# MCU.net
KiCad netlist of a schematic drawn in Altium Designer
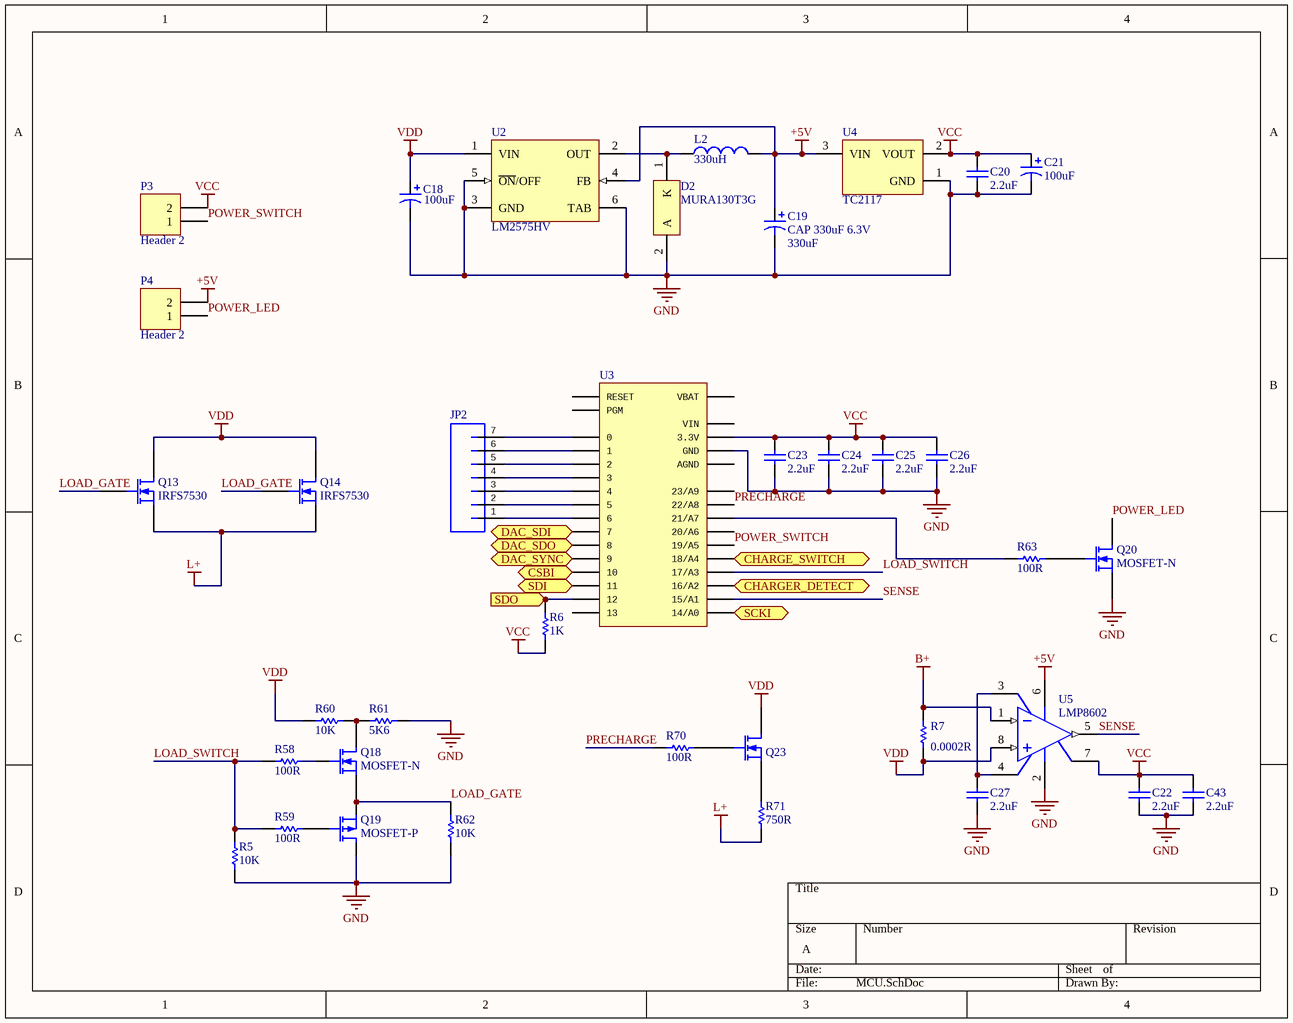
[diagram p0: MCU.SchDoc]

(export (version "E")
  (design (tool "Eeschema 10.0.6"))
  (components
    (comp (ref "C18")
      (value "100uF")
      (footprint "CAP 180uF 50V")
      (description "Polarized Capacitor (Axial)")
      (fields (field (name "PUBLISHER") "Altium Limited"))
      (libsource (lib "Components") (part "CAP 100uF 63V"))
    )
    (comp (ref "C19")
      (value "CAP 330uF 6.3V")
      (footprint "CAP 300uF 6.3V")
      (description "Polarized Capacitor (Axial)")
      (fields (field (name "ALTIUM_VALUE") "330uF") (field (name "PUBLISHER") "Altium Limited"))
      (libsource (lib "Components") (part "CAP 330uF 6.3V"))
    )
    (comp (ref "C20")
      (value "2.2uF")
      (footprint "CAPC0603(1608)55_N")
      (description "CAP 2.2uF 16V Â±10% 0603 (1608 Metric) Thickness 0.55mm SMD")
      (fields (field (name "TOLERANCE") "Â±10%"))
      (libsource (lib "Altium Content Vault") (part "CMP-1035-02762-1"))
    )
    (comp (ref "C21")
      (value "100uF")
      (footprint "AVX-CAPC7343_V")
      (description "Capacitor, Tantalum, 220uF 10% 10V MCCT-D (7343-31)")
      (fields (field (name "PARTNUMBER") "TAJD227K010R") (field (name "MANUFACTURER") "AVX"))
      (libsource (lib "Altium Content Vault") (part "CMP-0279-00002-1"))
    )
    (comp (ref "C22")
      (value "2.2uF")
      (footprint "CAPC0603(1608)55_M")
      (description "CAP 2.2uF 4V Â±10% 0603 (1608 Metric) Thickness 0.55mm SMD")
      (fields (field (name "TOLERANCE") "Â±10%"))
      (libsource (lib "Altium Content Vault") (part "CAP"))
    )
    (comp (ref "C23")
      (value "2.2uF")
      (footprint "CAPC0603(1608)55_N")
      (description "CAP 2.2uF 16V Â±10% 0603 (1608 Metric) Thickness 0.55mm SMD")
      (fields (field (name "TOLERANCE") "Â±10%"))
      (libsource (lib "Altium Content Vault") (part "CMP-1035-02762-1"))
    )
    (comp (ref "C24")
      (value "2.2uF")
      (footprint "CAPC0603(1608)55_N")
      (description "CAP 2.2uF 16V Â±10% 0603 (1608 Metric) Thickness 0.55mm SMD")
      (fields (field (name "TOLERANCE") "Â±10%"))
      (libsource (lib "Altium Content Vault") (part "CMP-1035-02762-1"))
    )
    (comp (ref "C25")
      (value "2.2uF")
      (footprint "CAPC0603(1608)55_N")
      (description "CAP 2.2uF 16V Â±10% 0603 (1608 Metric) Thickness 0.55mm SMD")
      (fields (field (name "TOLERANCE") "Â±10%"))
      (libsource (lib "Altium Content Vault") (part "CMP-1035-02762-1"))
    )
    (comp (ref "C26")
      (value "2.2uF")
      (footprint "CAPC0603(1608)55_N")
      (description "CAP 2.2uF 16V Â±10% 0603 (1608 Metric) Thickness 0.55mm SMD")
      (fields (field (name "TOLERANCE") "Â±10%"))
      (libsource (lib "Altium Content Vault") (part "CMP-1035-02762-1"))
    )
    (comp (ref "C27")
      (value "2.2uF")
      (footprint "CAPC0603(1608)55_N")
      (description "CAP 2.2uF 16V Â±10% 0603 (1608 Metric) Thickness 0.55mm SMD")
      (fields (field (name "TOLERANCE") "Â±10%"))
      (libsource (lib "Altium Content Vault") (part "CMP-1035-02762-1"))
    )
    (comp (ref "C43")
      (value "2.2uF")
      (footprint "CAPC0603(1608)55_M")
      (description "CAP 2.2uF 4V Â±10% 0603 (1608 Metric) Thickness 0.55mm SMD")
      (fields (field (name "TOLERANCE") "Â±10%"))
      (libsource (lib "Altium Content Vault") (part "CAP"))
    )
    (comp (ref "D2")
      (value "MURA130T3G")
      (footprint "ONSC-SMA-2-403D-02_V")
      (description "Surface Mount Ultrafast Power Rectifier, 2-Pin SMA, Pb-Free, Tape and Reel")
      (fields (field (name "MANUFACTURER") "On Semiconductor"))
      (libsource (lib "Altium Content Vault") (part "ONSC-D-K1A2-2_A"))
    )
    (comp (ref "JP2") (value "~") (footprint "JST-7-PTH") (libsource (lib "Components") (part "JST_7_RIGHT")))
    (comp (ref "L2")
      (value "330uH")
      (footprint "SDR1307")
      (description "Inductor")
      (fields (field (name "PUBLISHER") "Altium Limited"))
      (libsource (lib "Components") (part "SDR1307-331KL"))
    )
    (comp (ref "P3")
      (value "Header 2")
      (footprint "HDR1X2")
      (description "Header, 2-Pin")
      (fields (field (name "PUBLISHER") "Altium Limited"))
      (libsource (lib "Miscellaneous Connectors") (part "Header 2"))
    )
    (comp (ref "P4")
      (value "Header 2")
      (footprint "HDR1X2")
      (description "Header, 2-Pin")
      (fields (field (name "PUBLISHER") "Altium Limited"))
      (libsource (lib "Miscellaneous Connectors") (part "Header 2"))
    )
    (comp (ref "Q13")
      (value "IRFS7530")
      (footprint "DPAK127P1525X483-7N")
      (description "N-Channel MOSFET")
      (fields (field (name "PUBLISHER") "Altium Limited"))
      (libsource (lib "Components") (part "IRFS7530"))
    )
    (comp (ref "Q14")
      (value "IRFS7530")
      (footprint "DPAK127P1525X483-7N")
      (description "N-Channel MOSFET")
      (fields (field (name "PUBLISHER") "Altium Limited"))
      (libsource (lib "Components") (part "IRFS7530"))
    )
    (comp (ref "Q18")
      (value "MOSFET-N")
      (footprint "SOT23-3")
      (description "N-Channel MOSFET")
      (fields (field (name "PUBLISHER") "Altium Limited"))
      (libsource (lib "Components") (part "MOSFET-N"))
    )
    (comp (ref "Q19")
      (value "MOSFET-P")
      (footprint "SOT23-3")
      (description "P-Channel MOSFET")
      (fields (field (name "PUBLISHER") "Altium Limited"))
      (libsource (lib "Components") (part "MOSFET-P"))
    )
    (comp (ref "Q20")
      (value "MOSFET-N")
      (footprint "SOT23-3")
      (description "N-Channel MOSFET")
      (fields (field (name "PUBLISHER") "Altium Limited"))
      (libsource (lib "Components") (part "MOSFET-N"))
    )
    (comp (ref "Q23")
      (value "MOSFET-N")
      (footprint "SOT23-3")
      (description "N-Channel MOSFET")
      (fields (field (name "PUBLISHER") "Altium Limited"))
      (libsource (lib "Components") (part "MOSFET-N"))
    )
    (comp (ref "R5")
      (value "10K")
      (footprint "RESC0603(1608)_N")
      (description "10K 0.1W 1% 0603 (1608 Metric)  SMD")
      (fields (field (name "POWER") "0.1 W") (field (name "TOLERANCE") "1 %"))
      (libsource (lib "Altium Content Vault") (part "RES"))
    )
    (comp (ref "R6")
      (value "1K")
      (footprint "RESC0603(1608)_L")
      (description "1K 0.1W 5% 0603 (1608 Metric)  SMD")
      (fields (field (name "TOLERANCE") "5 %") (field (name "POWER") "0.1 W"))
      (libsource (lib "Altium Content Vault") (part "RES"))
    )
    (comp (ref "R7")
      (value "0.0002R")
      (footprint "WSLP5931")
      (description "Resistor")
      (fields (field (name "PUBLISHER") "Altium Limited"))
      (libsource (lib "Components") (part "SHUNT"))
    )
    (comp (ref "R58")
      (value "100R")
      (footprint "RESC0603(1608)_L")
      (description "100R 0.1W 5% 0603 (1608 Metric)  SMD")
      (fields (field (name "TOLERANCE") "5 %") (field (name "POWER") "0.1 W"))
      (libsource (lib "Altium Content Vault") (part "RES"))
    )
    (comp (ref "R59")
      (value "100R")
      (footprint "RESC0603(1608)_L")
      (description "100R 0.1W 5% 0603 (1608 Metric)  SMD")
      (fields (field (name "TOLERANCE") "5 %") (field (name "POWER") "0.1 W"))
      (libsource (lib "Altium Content Vault") (part "RES"))
    )
    (comp (ref "R60")
      (value "10K")
      (footprint "RESC0603(1608)_N")
      (description "10K 0.1W 5% 0603 (1608 Metric)  SMD")
      (fields (field (name "TOLERANCE") "5 %") (field (name "POWER") "0.1 W"))
      (libsource (lib "Altium Content Vault") (part "RES"))
    )
    (comp (ref "R61")
      (value "5K6")
      (footprint "RESC0603(1608)_M")
      (description "5K6 0.1W 1% 0603 (1608 Metric)  SMD")
      (fields (field (name "TOLERANCE") "1 %") (field (name "POWER") "0.1 W"))
      (libsource (lib "Altium Content Vault") (part "RES"))
    )
    (comp (ref "R62")
      (value "10K")
      (footprint "RESC0603(1608)_N")
      (description "10K 0.1W 1% 0603 (1608 Metric)  SMD")
      (fields (field (name "POWER") "0.1 W") (field (name "TOLERANCE") "1 %"))
      (libsource (lib "Altium Content Vault") (part "RES"))
    )
    (comp (ref "R63")
      (value "100R")
      (footprint "RESC0603(1608)_L")
      (description "100R 0.1W 5% 0603 (1608 Metric)  SMD")
      (fields (field (name "TOLERANCE") "5 %") (field (name "POWER") "0.1 W"))
      (libsource (lib "Altium Content Vault") (part "RES"))
    )
    (comp (ref "R70")
      (value "100R")
      (footprint "RESC0603(1608)_L")
      (description "100R 0.1W 5% 0603 (1608 Metric)  SMD")
      (fields (field (name "TOLERANCE") "5 %") (field (name "POWER") "0.1 W"))
      (libsource (lib "Altium Content Vault") (part "RES"))
    )
    (comp (ref "R71")
      (value "750R")
      (footprint "RESC2512(6432)_N")
      (description "750R 1W 1% 2512 (6432 Metric)  SMD")
      (fields (field (name "TOLERANCE") "1 %") (field (name "POWER") "1 W"))
      (libsource (lib "Altium Content Vault") (part "RES"))
    )
    (comp (ref "U2")
      (value "LM2575HV")
      (footprint "TS5B_L")
      (description "SIMPLE SWITCHERÂ® 1A Step-Down Voltage Regulator, 5-pin TO-263, Pb-Free")
      (fields (field (name "MANUFACTURER") "National Semiconductor"))
      (libsource (lib "Altium Content Vault") (part "PM-REG-LM2575HVS-12"))
    )
    (comp (ref "U3")
      (value "~")
      (footprint "TEENSY_3.0_BASIC")
      (libsource (lib "Components") (part "TEENSY_3.0_BASIC"))
    )
    (comp (ref "U4")
      (value "TC2117")
      (footprint "SOT-223-DB3_M")
      (libsource (lib "Components") (part "PM-LINEREG-TC2117-IL4"))
    )
    (comp (ref "U5")
      (value "LMP8602")
      (footprint "M08A_M")
      (description "60V Common Mode, 50 x Gain, Bidirectional Precision Current Sensing Amplifier, 8 pin SOIC NARROW")
      (fields (field (name "MANUFACTURER") "National Semiconductor"))
      (libsource (lib "Altium Content Vault") (part "AMP-SEN-LMP8601-8"))
    )
  )
  (nets
    (net (code "1") (name "+5V") (class "Default")
      (node (ref "C19") (pin "1") (pinfunction "1_1") (pintype "passive"))
      (node (ref "L2") (pin "2") (pinfunction "2_2") (pintype "passive"))
      (node (ref "P4") (pin "2") (pinfunction "2_2") (pintype "passive"))
      (node (ref "U2") (pin "4") (pinfunction "FB_4") (pintype "input"))
      (node (ref "U4") (pin "3") (pinfunction "VIN_3") (pintype "power_in"))
      (node (ref "U5") (pin "6") (pinfunction "VS_6") (pintype "power_in"))
    )
    (net (code "2") (name "/CHARGER_DETECT") (class "Default")
      (node (ref "U3") (pin "16/A2") (pinfunction "16/A2_16/A2") (pintype "passive"))
    )
    (net (code "3") (name "/CHARGE_SWITCH") (class "Default")
      (node (ref "U3") (pin "18/A4") (pinfunction "18/A4_18/A4") (pintype "passive"))
    )
    (net (code "4") (name "/CSBI") (class "Default")
      (node (ref "U3") (pin "10") (pinfunction "10_10") (pintype "passive"))
    )
    (net (code "5") (name "/DAC_SDI") (class "Default")
      (node (ref "U3") (pin "7") (pinfunction "7_7") (pintype "passive"))
    )
    (net (code "6") (name "/DAC_SDO") (class "Default")
      (node (ref "U3") (pin "8") (pinfunction "8_8") (pintype "passive"))
    )
    (net (code "7") (name "/DAC_SYNC") (class "Default")
      (node (ref "U3") (pin "9") (pinfunction "9_9") (pintype "passive"))
    )
    (net (code "8") (name "/LOAD_GATE") (class "Default")
      (node (ref "Q13") (pin "2") (pinfunction "G_2") (pintype "passive"))
      (node (ref "Q14") (pin "2") (pinfunction "G_2") (pintype "passive"))
      (node (ref "Q18") (pin "3") (pinfunction "S_3") (pintype "passive"))
      (node (ref "Q19") (pin "3") (pinfunction "S_3") (pintype "passive"))
      (node (ref "R62") (pin "2") (pinfunction "2_2") (pintype "passive"))
    )
    (net (code "9") (name "/LOAD_SWITCH") (class "Default")
      (node (ref "R5") (pin "2") (pinfunction "2_2") (pintype "passive"))
      (node (ref "R58") (pin "1") (pinfunction "1_1") (pintype "passive"))
      (node (ref "R59") (pin "1") (pinfunction "1_1") (pintype "passive"))
      (node (ref "U3") (pin "17/A3") (pinfunction "17/A3_17/A3") (pintype "passive"))
    )
    (net (code "10") (name "/POWER_LED") (class "Default")
      (node (ref "P4") (pin "1") (pinfunction "1_1") (pintype "passive"))
      (node (ref "Q20") (pin "2") (pinfunction "D_2") (pintype "passive"))
    )
    (net (code "11") (name "/POWER_SWITCH") (class "Default")
      (node (ref "P3") (pin "1") (pinfunction "1_1") (pintype "passive"))
      (node (ref "U3") (pin "19/A5") (pinfunction "19/A5_19/A5") (pintype "passive"))
    )
    (net (code "12") (name "/PRECHARGE") (class "Default")
      (node (ref "R70") (pin "1") (pinfunction "1_1") (pintype "passive"))
      (node (ref "U3") (pin "22/A8") (pinfunction "22/A8_22/A8") (pintype "passive"))
    )
    (net (code "13") (name "/SCKI") (class "Default")
      (node (ref "U3") (pin "14/A0") (pinfunction "14/A0_14/A0") (pintype "passive"))
    )
    (net (code "14") (name "/SDI") (class "Default")
      (node (ref "U3") (pin "11") (pinfunction "11_11") (pintype "passive"))
    )
    (net (code "15") (name "/SDO") (class "Default")
      (node (ref "R6") (pin "2") (pinfunction "2_2") (pintype "passive"))
      (node (ref "U3") (pin "12") (pinfunction "12_12") (pintype "passive"))
    )
    (net (code "16") (name "/SENSE") (class "Default")
      (node (ref "U3") (pin "15/A1") (pinfunction "15/A1_15/A1") (pintype "passive"))
      (node (ref "U5") (pin "5") (pinfunction "OUT_5") (pintype "output"))
    )
    (net (code "17") (name "B+") (class "Default")
      (node (ref "R7") (pin "2") (pinfunction "2_2") (pintype "passive"))
      (node (ref "U5") (pin "1") (pinfunction "IN-_1") (pintype "input"))
    )
    (net (code "18") (name "GND") (class "Default")
      (node (ref "C18") (pin "2") (pinfunction "2_2") (pintype "passive"))
      (node (ref "C19") (pin "2") (pinfunction "2_2") (pintype "passive"))
      (node (ref "C20") (pin "2") (pinfunction "2_2") (pintype "passive"))
      (node (ref "C21") (pin "2") (pinfunction "2_2") (pintype "passive"))
      (node (ref "C22") (pin "1") (pinfunction "1_1") (pintype "passive"))
      (node (ref "C23") (pin "1") (pinfunction "1_1") (pintype "passive"))
      (node (ref "C24") (pin "1") (pinfunction "1_1") (pintype "passive"))
      (node (ref "C25") (pin "1") (pinfunction "1_1") (pintype "passive"))
      (node (ref "C26") (pin "1") (pinfunction "1_1") (pintype "passive"))
      (node (ref "C27") (pin "1") (pinfunction "1_1") (pintype "passive"))
      (node (ref "C43") (pin "1") (pinfunction "1_1") (pintype "passive"))
      (node (ref "D2") (pin "2") (pinfunction "A_2") (pintype "passive"))
      (node (ref "Q19") (pin "2") (pinfunction "D_2") (pintype "passive"))
      (node (ref "Q20") (pin "3") (pinfunction "S_3") (pintype "passive"))
      (node (ref "R5") (pin "1") (pinfunction "1_1") (pintype "passive"))
      (node (ref "R61") (pin "1") (pinfunction "1_1") (pintype "passive"))
      (node (ref "R62") (pin "1") (pinfunction "1_1") (pintype "passive"))
      (node (ref "U2") (pin "3") (pinfunction "GND_3") (pintype "power_in"))
      (node (ref "U2") (pin "5") (pinfunction "~{ON}/OFF_5") (pintype "input"))
      (node (ref "U2") (pin "6") (pinfunction "TAB_6") (pintype "power_in"))
      (node (ref "U3") (pin "GND_GND1") (pinfunction "GND_GND_GND1") (pintype "power_in"))
      (node (ref "U4") (pin "1") (pinfunction "GND_1") (pintype "power_in"))
      (node (ref "U5") (pin "2") (pinfunction "GND_2") (pintype "power_in"))
    )
    (net (code "19") (name "L+") (class "Default")
      (node (ref "Q13") (pin "3") (pinfunction "S_3") (pintype "passive"))
      (node (ref "Q14") (pin "3") (pinfunction "S_3") (pintype "passive"))
      (node (ref "R71") (pin "1") (pinfunction "1_1") (pintype "passive"))
    )
    (net (code "20") (name "Net-(D2-K)") (class "Default")
      (node (ref "D2") (pin "1") (pinfunction "K_1") (pintype "passive"))
      (node (ref "L2") (pin "1") (pinfunction "1_1") (pintype "passive"))
      (node (ref "U2") (pin "2") (pinfunction "OUT_2") (pintype "power_in"))
    )
    (net (code "21") (name "Net-(JP2-Pad1)") (class "Default")
      (node (ref "JP2") (pin "1") (pinfunction "1_1") (pintype "passive"))
      (node (ref "U3") (pin "6") (pinfunction "6_6") (pintype "passive"))
    )
    (net (code "22") (name "Net-(JP2-Pad2)") (class "Default")
      (node (ref "JP2") (pin "2") (pinfunction "2_2") (pintype "passive"))
      (node (ref "U3") (pin "5") (pinfunction "5_5") (pintype "passive"))
    )
    (net (code "23") (name "Net-(JP2-Pad3)") (class "Default")
      (node (ref "JP2") (pin "3") (pinfunction "3_3") (pintype "passive"))
      (node (ref "U3") (pin "4") (pinfunction "4_4") (pintype "passive"))
    )
    (net (code "24") (name "Net-(JP2-Pad4)") (class "Default")
      (node (ref "JP2") (pin "4") (pinfunction "4_4") (pintype "passive"))
      (node (ref "U3") (pin "3") (pinfunction "3_3") (pintype "passive"))
    )
    (net (code "25") (name "Net-(JP2-Pad5)") (class "Default")
      (node (ref "JP2") (pin "5") (pinfunction "5_5") (pintype "passive"))
      (node (ref "U3") (pin "2") (pinfunction "2_2") (pintype "passive"))
    )
    (net (code "26") (name "Net-(JP2-Pad6)") (class "Default")
      (node (ref "JP2") (pin "6") (pinfunction "6_6") (pintype "passive"))
      (node (ref "U3") (pin "1") (pinfunction "1_1") (pintype "passive"))
    )
    (net (code "27") (name "Net-(JP2-Pad7)") (class "Default")
      (node (ref "JP2") (pin "7") (pinfunction "7_7") (pintype "passive"))
      (node (ref "U3") (pin "0") (pinfunction "0_0") (pintype "passive"))
    )
    (net (code "28") (name "Net-(Q18-D)") (class "Default")
      (node (ref "Q18") (pin "2") (pinfunction "D_2") (pintype "passive"))
      (node (ref "R60") (pin "1") (pinfunction "1_1") (pintype "passive"))
      (node (ref "R61") (pin "2") (pinfunction "2_2") (pintype "passive"))
    )
    (net (code "29") (name "Net-(Q18-G)") (class "Default")
      (node (ref "Q18") (pin "1") (pinfunction "G_1") (pintype "passive"))
      (node (ref "R58") (pin "2") (pinfunction "2_2") (pintype "passive"))
    )
    (net (code "30") (name "Net-(Q19-G)") (class "Default")
      (node (ref "Q19") (pin "1") (pinfunction "G_1") (pintype "passive"))
      (node (ref "R59") (pin "2") (pinfunction "2_2") (pintype "passive"))
    )
    (net (code "31") (name "Net-(Q20-G)") (class "Default")
      (node (ref "Q20") (pin "1") (pinfunction "G_1") (pintype "passive"))
      (node (ref "R63") (pin "2") (pinfunction "2_2") (pintype "passive"))
    )
    (net (code "32") (name "Net-(Q23-G)") (class "Default")
      (node (ref "Q23") (pin "1") (pinfunction "G_1") (pintype "passive"))
      (node (ref "R70") (pin "2") (pinfunction "2_2") (pintype "passive"))
    )
    (net (code "33") (name "Net-(Q23-S)") (class "Default")
      (node (ref "Q23") (pin "3") (pinfunction "S_3") (pintype "passive"))
      (node (ref "R71") (pin "2") (pinfunction "2_2") (pintype "passive"))
    )
    (net (code "34") (name "Net-(R63-Pad1)") (class "Default")
      (node (ref "R63") (pin "1") (pinfunction "1_1") (pintype "passive"))
      (node (ref "U3") (pin "21/A7") (pinfunction "21/A7_21/A7") (pintype "passive"))
    )
    (net (code "35") (name "Net-(U5-A1)") (class "Default")
      (node (ref "C27") (pin "2") (pinfunction "2_2") (pintype "passive"))
      (node (ref "U5") (pin "3") (pinfunction "A1_3") (pintype "passive"))
      (node (ref "U5") (pin "4") (pinfunction "A2_4") (pintype "passive"))
    )
    (net (code "36") (name "VCC") (class "Default")
      (node (ref "C20") (pin "1") (pinfunction "1_1") (pintype "passive"))
      (node (ref "C21") (pin "1") (pinfunction "1_1") (pintype "passive"))
      (node (ref "C22") (pin "2") (pinfunction "2_2") (pintype "passive"))
      (node (ref "C23") (pin "2") (pinfunction "2_2") (pintype "passive"))
      (node (ref "C24") (pin "2") (pinfunction "2_2") (pintype "passive"))
      (node (ref "C25") (pin "2") (pinfunction "2_2") (pintype "passive"))
      (node (ref "C26") (pin "2") (pinfunction "2_2") (pintype "passive"))
      (node (ref "C43") (pin "2") (pinfunction "2_2") (pintype "passive"))
      (node (ref "P3") (pin "2") (pinfunction "2_2") (pintype "passive"))
      (node (ref "R6") (pin "1") (pinfunction "1_1") (pintype "passive"))
      (node (ref "U3") (pin "3.3V_3.3V1") (pinfunction "3.3V_3.3V_3.3V1") (pintype "power_in"))
      (node (ref "U4") (pin "2") (pinfunction "VOUT_2") (pintype "power_in"))
      (node (ref "U5") (pin "7") (pinfunction "OFS_7") (pintype "passive"))
    )
    (net (code "37") (name "VDD") (class "Default")
      (node (ref "C18") (pin "1") (pinfunction "1_1") (pintype "passive"))
      (node (ref "Q13") (pin "1") (pinfunction "D_1") (pintype "passive"))
      (node (ref "Q14") (pin "1") (pinfunction "D_1") (pintype "passive"))
      (node (ref "Q23") (pin "2") (pinfunction "D_2") (pintype "passive"))
      (node (ref "R60") (pin "2") (pinfunction "2_2") (pintype "passive"))
      (node (ref "R7") (pin "1") (pinfunction "1_1") (pintype "passive"))
      (node (ref "U2") (pin "1") (pinfunction "VIN_1") (pintype "power_in"))
      (node (ref "U5") (pin "8") (pinfunction "IN+_8") (pintype "input"))
    )
    (net (code "38") (name "unconnected-(U3-Pad13)") (class "Default")
      (node (ref "U3") (pin "13") (pinfunction "13_13") (pintype "passive"))
    )
    (net (code "39") (name "unconnected-(U3-Pad20{slash}A6)") (class "Default")
      (node (ref "U3") (pin "20/A6") (pinfunction "20/A6_20/A6") (pintype "passive"))
    )
    (net (code "40") (name "unconnected-(U3-Pad23{slash}A9)") (class "Default")
      (node (ref "U3") (pin "23/A9") (pinfunction "23/A9_23/A9") (pintype "passive"))
    )
    (net (code "41") (name "unconnected-(U3-PadAGND)") (class "Default")
      (node (ref "U3") (pin "AGND") (pinfunction "AGND_AGND") (pintype "power_in"))
    )
    (net (code "42") (name "unconnected-(U3-PadPGM)") (class "Default")
      (node (ref "U3") (pin "PGM") (pinfunction "PGM_PGM") (pintype "passive"))
    )
    (net (code "43") (name "unconnected-(U3-PadRESET)") (class "Default")
      (node (ref "U3") (pin "RESET") (pinfunction "RESET_RESET") (pintype "passive"))
    )
    (net (code "44") (name "unconnected-(U3-PadVBAT)") (class "Default")
      (node (ref "U3") (pin "VBAT") (pinfunction "VBAT_VBAT") (pintype "power_in"))
    )
    (net (code "45") (name "unconnected-(U3-PadVIN)") (class "Default")
      (node (ref "U3") (pin "VIN") (pinfunction "VIN_VIN") (pintype "power_in"))
    )
  )
)
